# Motor_Interface.net
KiCad netlist of a schematic drawn in Altium Designer
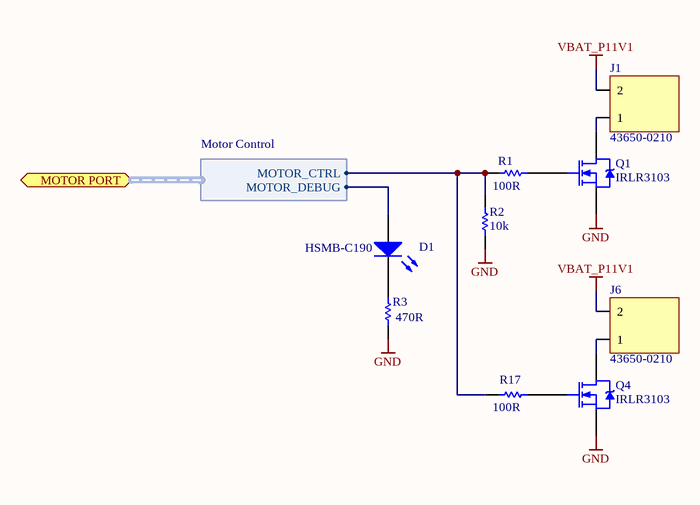
[diagram p0: Motor Interface.SchDoc]

(export (version "E")
  (design (tool "Eeschema 10.0.6"))
  (components
    (comp (ref "D1")
      (value "HSMB-C190")
      (footprint "1.6X0.8X0.8")
      (description "Blue Surface Mount Chip LED, Blue")
      (fields (field (name "PUBLISHER") "Altium Limited"))
      (libsource (lib "Avago Optoelectronic LED") (part "HSMB-C190"))
    )
    (comp (ref "J1")
      (value "43650-0210")
      (footprint "43650-0210")
      (description "Power Connector, Micro-Fit 3.0 Header, SMT, Single Row, Right Angle, 2 Circuits")
      (libsource (lib "Molex Power Connector") (part "43650-0210"))
    )
    (comp (ref "J6")
      (value "43650-0210")
      (footprint "43650-0210")
      (description "Power Connector, Micro-Fit 3.0 Header, SMT, Single Row, Right Angle, 2 Circuits")
      (libsource (lib "Molex Power Connector") (part "43650-0210"))
    )
    (comp (ref "Q1")
      (value "IRLR3103")
      (footprint "TO-252AA_N")
      (description "HEXFET Power MOSFET")
      (fields (field (name "PUBLISHER") "Altium Limited"))
      (libsource (lib "IR Discrete MOSFET - Power") (part "IRLR3103"))
    )
    (comp (ref "Q4")
      (value "IRLR3103")
      (footprint "TO-252AA_N")
      (description "HEXFET Power MOSFET")
      (fields (field (name "PUBLISHER") "Altium Limited"))
      (libsource (lib "IR Discrete MOSFET - Power") (part "IRLR3103"))
    )
    (comp (ref "R1")
      (value "100R")
      (footprint "3-0603")
      (description "Thick Film Chip Resistor, 1 Ohm to 10M Ohm Range, 5% Tolerance, 0603 Size, 0.1 W")
      (fields (field (name "Comment") "ERJ3GEYJ101V") (field (name "PUBLISHER") "Altium Limited"))
      (libsource (lib "Panasonic Resistor") (part "ERJ3GE"))
    )
    (comp (ref "R2")
      (value "10k")
      (footprint "3-0603")
      (description "Thick Film Chip Resistor, 1 Ohm to 10M Ohm Range, 5% Tolerance, 0603 Size, 0.1 W")
      (fields (field (name "Comment") "ERJ3GEYJ103V") (field (name "PUBLISHER") "Altium Limited"))
      (libsource (lib "Panasonic Resistor") (part "ERJ3GE"))
    )
    (comp (ref "R3")
      (value "470R")
      (footprint "3-0603")
      (description "Thick Film Chip Resistor, 1 Ohm to 10M Ohm Range, 5% Tolerance, 0603 Size, 0.1 W")
      (fields (field (name "Comment") "ERJ3GEYJ471V") (field (name "PUBLISHER") "Altium Limited"))
      (libsource (lib "Panasonic Resistor") (part "ERJ3GE"))
    )
    (comp (ref "R17")
      (value "100R")
      (footprint "3-0603")
      (description "Thick Film Chip Resistor, 1 Ohm to 10M Ohm Range, 5% Tolerance, 0603 Size, 0.1 W")
      (fields (field (name "Comment") "ERJ3GEYJ101V") (field (name "PUBLISHER") "Altium Limited"))
      (libsource (lib "Panasonic Resistor") (part "ERJ3GE"))
    )
  )
  (nets
    (net (code "3") (name "/MOTOR_CTRL") (class "Default")
      (node (ref "R1") (pin "1") (pinfunction "1_1") (pintype "passive"))
      (node (ref "R17") (pin "1") (pinfunction "1_1") (pintype "passive"))
      (node (ref "R2") (pin "1") (pinfunction "1_1") (pintype "passive"))
    )
    (net (code "4") (name "/MOTOR_DEBUG") (class "Default")
      (node (ref "D1") (pin "1") (pinfunction "A_1") (pintype "passive"))
    )
    (net (code "6") (name "GND") (class "Default")
      (node (ref "Q1") (pin "3") (pinfunction "S_3") (pintype "passive"))
      (node (ref "Q4") (pin "3") (pinfunction "S_3") (pintype "passive"))
      (node (ref "R2") (pin "2") (pinfunction "2_2") (pintype "passive"))
      (node (ref "R3") (pin "1") (pinfunction "1_1") (pintype "passive"))
    )
    (net (code "7") (name "Net-(D1-K)") (class "Default")
      (node (ref "D1") (pin "2") (pinfunction "K_2") (pintype "passive"))
      (node (ref "R3") (pin "2") (pinfunction "2_2") (pintype "passive"))
    )
    (net (code "8") (name "Net-(Q1-D)") (class "Default")
      (node (ref "J1") (pin "1") (pinfunction "1_1") (pintype "power_in"))
      (node (ref "Q1") (pin "4") (pinfunction "D_4") (pintype "passive"))
    )
    (net (code "9") (name "Net-(Q1-G)") (class "Default")
      (node (ref "Q1") (pin "1") (pinfunction "G_1") (pintype "passive"))
      (node (ref "R1") (pin "2") (pinfunction "2_2") (pintype "passive"))
    )
    (net (code "10") (name "Net-(Q4-D)") (class "Default")
      (node (ref "J6") (pin "1") (pinfunction "1_1") (pintype "power_in"))
      (node (ref "Q4") (pin "4") (pinfunction "D_4") (pintype "passive"))
    )
    (net (code "11") (name "Net-(Q4-G)") (class "Default")
      (node (ref "Q4") (pin "1") (pinfunction "G_1") (pintype "passive"))
      (node (ref "R17") (pin "2") (pinfunction "2_2") (pintype "passive"))
    )
    (net (code "12") (name "VBAT_P11V1") (class "Default")
      (node (ref "J1") (pin "2") (pinfunction "2_2") (pintype "power_in"))
      (node (ref "J6") (pin "2") (pinfunction "2_2") (pintype "power_in"))
    )
  )
)
